# line_sensor_board.net
KiCad netlist of a schematic drawn in EAGLE
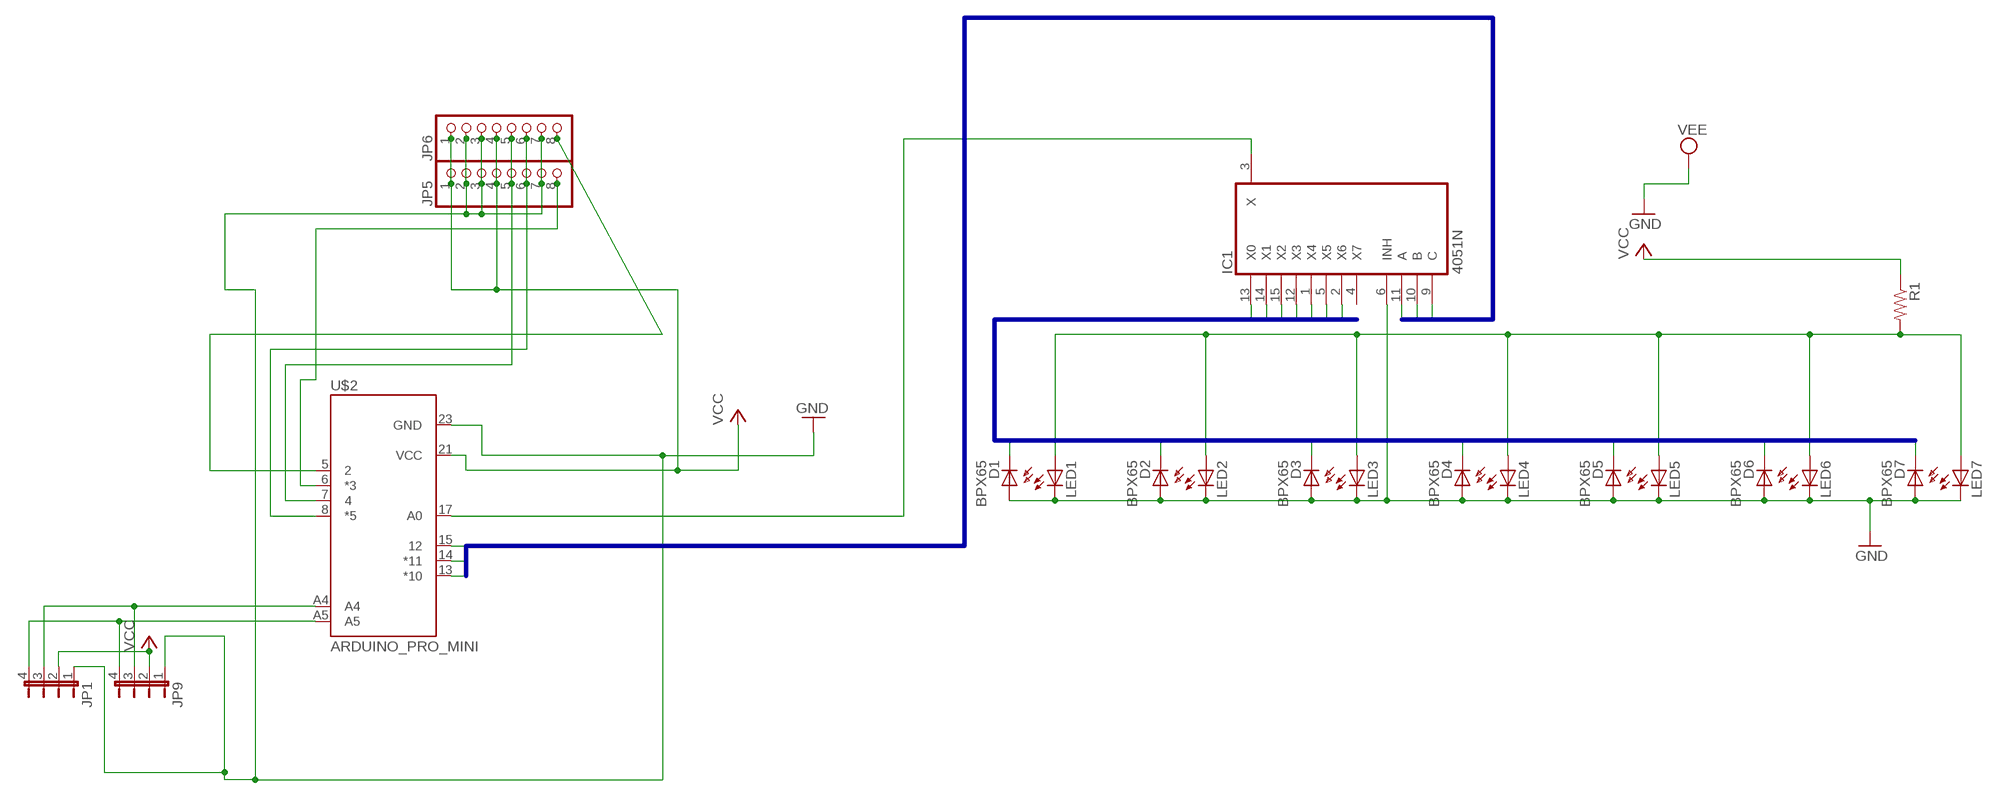
[diagram p0: schematic, sheet 1]

(export (version "E")
  (design (tool "Eeschema 10.0.6"))
  (components
    (comp (ref "D1")
      (value "BPX65")
      (footprint "eagle-import:BPX65")
      (fields (field (name "MPN") "BPX65."))
      (libsource (lib "eagle-import") (part "BPX65"))
    )
    (comp (ref "D2")
      (value "BPX65")
      (footprint "eagle-import:BPX65")
      (fields (field (name "MPN") "BPX65."))
      (libsource (lib "eagle-import") (part "BPX65"))
    )
    (comp (ref "D3")
      (value "BPX65")
      (footprint "eagle-import:BPX65")
      (fields (field (name "MPN") "BPX65."))
      (libsource (lib "eagle-import") (part "BPX65"))
    )
    (comp (ref "D4")
      (value "BPX65")
      (footprint "eagle-import:BPX65")
      (fields (field (name "MPN") "BPX65."))
      (libsource (lib "eagle-import") (part "BPX65"))
    )
    (comp (ref "D5")
      (value "BPX65")
      (footprint "eagle-import:BPX65")
      (fields (field (name "MPN") "BPX65."))
      (libsource (lib "eagle-import") (part "BPX65"))
    )
    (comp (ref "D6")
      (value "BPX65")
      (footprint "eagle-import:BPX65")
      (fields (field (name "MPN") "BPX65."))
      (libsource (lib "eagle-import") (part "BPX65"))
    )
    (comp (ref "D7")
      (value "BPX65")
      (footprint "eagle-import:BPX65")
      (fields (field (name "MPN") "BPX65."))
      (libsource (lib "eagle-import") (part "BPX65"))
    )
    (comp (ref "IC1")
      (value "4051N")
      (footprint "eagle-import:DIL16")
      (libsource (lib "eagle-import") (part "4051N"))
    )
    (comp (ref "JP1")
      (value "JP4E")
      (footprint "eagle-import:JP4")
      (libsource (lib "eagle-import") (part "JP4E"))
    )
    (comp (ref "JP5")
      (value "PINHD-1X8")
      (footprint "eagle-import:1X08")
      (libsource (lib "eagle-import") (part "PINHD-1X8"))
    )
    (comp (ref "JP6")
      (value "PINHD-1X8")
      (footprint "eagle-import:1X08")
      (libsource (lib "eagle-import") (part "PINHD-1X8"))
    )
    (comp (ref "JP9")
      (value "JP4E")
      (footprint "eagle-import:JP4")
      (libsource (lib "eagle-import") (part "JP4E"))
    )
    (comp (ref "LED1")
      (value "LED3MM")
      (footprint "eagle-import:LED3MM")
      (libsource (lib "eagle-import") (part "LED3MM"))
    )
    (comp (ref "LED2")
      (value "LED3MM")
      (footprint "eagle-import:LED3MM")
      (libsource (lib "eagle-import") (part "LED3MM"))
    )
    (comp (ref "LED3")
      (value "LED3MM")
      (footprint "eagle-import:LED3MM")
      (libsource (lib "eagle-import") (part "LED3MM"))
    )
    (comp (ref "LED4")
      (value "LED3MM")
      (footprint "eagle-import:LED3MM")
      (libsource (lib "eagle-import") (part "LED3MM"))
    )
    (comp (ref "LED5")
      (value "LED3MM")
      (footprint "eagle-import:LED3MM")
      (libsource (lib "eagle-import") (part "LED3MM"))
    )
    (comp (ref "LED6")
      (value "LED3MM")
      (footprint "eagle-import:LED3MM")
      (libsource (lib "eagle-import") (part "LED3MM"))
    )
    (comp (ref "LED7")
      (value "LED3MM")
      (footprint "eagle-import:LED3MM")
      (libsource (lib "eagle-import") (part "LED3MM"))
    )
    (comp (ref "R1")
      (value "R-US_0204/5")
      (footprint "eagle-import:0204_5")
      (libsource (lib "eagle-import") (part "R-US_0204/5"))
    )
    (comp (ref "U$2")
      (value "ARDUINO_PRO_MINI")
      (footprint "eagle-import:ARDUINO_PRO_MINI")
      (libsource (lib "eagle-import") (part "ARDUINO_PRO_MINI"))
    )
  )
  (nets
    (net (code "1") (name "/A1") (class "Default")
      (node (ref "IC1") (pin "11") (pinfunction "A_11") (pintype "input"))
      (node (ref "U$2") (pin "15") (pinfunction "12_15") (pintype "bidirectional"))
    )
    (net (code "2") (name "/A2") (class "Default")
      (node (ref "IC1") (pin "10") (pinfunction "B_10") (pintype "input"))
      (node (ref "U$2") (pin "14") (pinfunction "*11_14") (pintype "bidirectional"))
    )
    (net (code "3") (name "/A3") (class "Default")
      (node (ref "IC1") (pin "9") (pinfunction "C_9") (pintype "input"))
      (node (ref "U$2") (pin "13") (pinfunction "*10_13") (pintype "bidirectional"))
    )
    (net (code "4") (name "/B1") (class "Default")
      (node (ref "D7") (pin "K") (pinfunction "C_K") (pintype "passive"))
      (node (ref "IC1") (pin "13") (pinfunction "X0_13") (pintype "bidirectional"))
    )
    (net (code "5") (name "/B2") (class "Default")
      (node (ref "D6") (pin "K") (pinfunction "C_K") (pintype "passive"))
      (node (ref "IC1") (pin "14") (pinfunction "X1_14") (pintype "bidirectional"))
    )
    (net (code "6") (name "/B3") (class "Default")
      (node (ref "D5") (pin "K") (pinfunction "C_K") (pintype "passive"))
      (node (ref "IC1") (pin "15") (pinfunction "X2_15") (pintype "bidirectional"))
    )
    (net (code "7") (name "/B4") (class "Default")
      (node (ref "D4") (pin "K") (pinfunction "C_K") (pintype "passive"))
      (node (ref "IC1") (pin "12") (pinfunction "X3_12") (pintype "bidirectional"))
    )
    (net (code "8") (name "/B5") (class "Default")
      (node (ref "D3") (pin "K") (pinfunction "C_K") (pintype "passive"))
      (node (ref "IC1") (pin "1") (pinfunction "X4_1") (pintype "bidirectional"))
    )
    (net (code "9") (name "/B6") (class "Default")
      (node (ref "D2") (pin "K") (pinfunction "C_K") (pintype "passive"))
      (node (ref "IC1") (pin "5") (pinfunction "X5_5") (pintype "bidirectional"))
    )
    (net (code "10") (name "/B7") (class "Default")
      (node (ref "D1") (pin "K") (pinfunction "C_K") (pintype "passive"))
      (node (ref "IC1") (pin "2") (pinfunction "X6_2") (pintype "bidirectional"))
    )
    (net (code "11") (name "GND") (class "Default")
      (node (ref "D1") (pin "A") (pinfunction "A_A") (pintype "passive"))
      (node (ref "D2") (pin "A") (pinfunction "A_A") (pintype "passive"))
      (node (ref "D3") (pin "A") (pinfunction "A_A") (pintype "passive"))
      (node (ref "D4") (pin "A") (pinfunction "A_A") (pintype "passive"))
      (node (ref "D5") (pin "A") (pinfunction "A_A") (pintype "passive"))
      (node (ref "D6") (pin "A") (pinfunction "A_A") (pintype "passive"))
      (node (ref "D7") (pin "A") (pinfunction "A_A") (pintype "passive"))
      (node (ref "IC1") (pin "6") (pinfunction "INH_6") (pintype "input"))
      (node (ref "JP1") (pin "1") (pinfunction "1_1") (pintype "passive"))
      (node (ref "JP5") (pin "2") (pinfunction "2_2") (pintype "passive"))
      (node (ref "JP5") (pin "3") (pinfunction "3_3") (pintype "passive"))
      (node (ref "JP5") (pin "7") (pinfunction "7_7") (pintype "passive"))
      (node (ref "JP6") (pin "2") (pinfunction "2_2") (pintype "passive"))
      (node (ref "JP6") (pin "3") (pinfunction "3_3") (pintype "passive"))
      (node (ref "JP6") (pin "7") (pinfunction "7_7") (pintype "passive"))
      (node (ref "JP9") (pin "1") (pinfunction "1_1") (pintype "passive"))
      (node (ref "LED1") (pin "K") (pinfunction "C_K") (pintype "passive"))
      (node (ref "LED2") (pin "K") (pinfunction "C_K") (pintype "passive"))
      (node (ref "LED3") (pin "K") (pinfunction "C_K") (pintype "passive"))
      (node (ref "LED4") (pin "K") (pinfunction "C_K") (pintype "passive"))
      (node (ref "LED5") (pin "K") (pinfunction "C_K") (pintype "passive"))
      (node (ref "LED6") (pin "K") (pinfunction "C_K") (pintype "passive"))
      (node (ref "LED7") (pin "K") (pinfunction "C_K") (pintype "passive"))
      (node (ref "U$2") (pin "23") (pinfunction "GND_23") (pintype "bidirectional"))
    )
    (net (code "12") (name "Net-(IC1A-X)") (class "Default")
      (node (ref "IC1") (pin "3") (pinfunction "X_3") (pintype "bidirectional"))
      (node (ref "U$2") (pin "17") (pinfunction "A0_17") (pintype "bidirectional"))
    )
    (net (code "13") (name "Net-(JP1-Pad3)") (class "Default")
      (node (ref "JP1") (pin "3") (pinfunction "3_3") (pintype "passive"))
      (node (ref "JP9") (pin "3") (pinfunction "3_3") (pintype "passive"))
      (node (ref "U$2") (pin "A4") (pinfunction "A4_A4") (pintype "bidirectional"))
    )
    (net (code "14") (name "Net-(JP1-Pad4)") (class "Default")
      (node (ref "JP1") (pin "4") (pinfunction "4_4") (pintype "passive"))
      (node (ref "JP9") (pin "4") (pinfunction "4_4") (pintype "passive"))
      (node (ref "U$2") (pin "A5") (pinfunction "A5_A5") (pintype "bidirectional"))
    )
    (net (code "15") (name "Net-(LED1-PadA)") (class "Default")
      (node (ref "LED1") (pin "A") (pinfunction "A_A") (pintype "passive"))
      (node (ref "LED2") (pin "A") (pinfunction "A_A") (pintype "passive"))
      (node (ref "LED3") (pin "A") (pinfunction "A_A") (pintype "passive"))
      (node (ref "LED4") (pin "A") (pinfunction "A_A") (pintype "passive"))
      (node (ref "LED5") (pin "A") (pinfunction "A_A") (pintype "passive"))
      (node (ref "LED6") (pin "A") (pinfunction "A_A") (pintype "passive"))
      (node (ref "LED7") (pin "A") (pinfunction "A_A") (pintype "passive"))
      (node (ref "R1") (pin "2") (pinfunction "2_2") (pintype "passive"))
    )
    (net (code "16") (name "Net-(U$2-*3)") (class "Default")
      (node (ref "JP5") (pin "8") (pinfunction "8_8") (pintype "passive"))
      (node (ref "U$2") (pin "6") (pinfunction "*3_6") (pintype "bidirectional"))
    )
    (net (code "17") (name "Net-(U$2-*5)") (class "Default")
      (node (ref "JP5") (pin "6") (pinfunction "6_6") (pintype "passive"))
      (node (ref "JP6") (pin "6") (pinfunction "6_6") (pintype "passive"))
      (node (ref "U$2") (pin "8") (pinfunction "*5_8") (pintype "bidirectional"))
    )
    (net (code "18") (name "Net-(U$2-2)") (class "Default")
      (node (ref "JP6") (pin "8") (pinfunction "8_8") (pintype "passive"))
      (node (ref "U$2") (pin "5") (pinfunction "2_5") (pintype "bidirectional"))
    )
    (net (code "19") (name "Net-(U$2-4)") (class "Default")
      (node (ref "JP5") (pin "5") (pinfunction "5_5") (pintype "passive"))
      (node (ref "JP6") (pin "5") (pinfunction "5_5") (pintype "passive"))
      (node (ref "U$2") (pin "7") (pinfunction "4_7") (pintype "bidirectional"))
    )
    (net (code "20") (name "VCC") (class "Default")
      (node (ref "JP1") (pin "2") (pinfunction "2_2") (pintype "passive"))
      (node (ref "JP5") (pin "1") (pinfunction "1_1") (pintype "passive"))
      (node (ref "JP5") (pin "4") (pinfunction "4_4") (pintype "passive"))
      (node (ref "JP6") (pin "1") (pinfunction "1_1") (pintype "passive"))
      (node (ref "JP6") (pin "4") (pinfunction "4_4") (pintype "passive"))
      (node (ref "JP9") (pin "2") (pinfunction "2_2") (pintype "passive"))
      (node (ref "R1") (pin "1") (pinfunction "1_1") (pintype "passive"))
      (node (ref "U$2") (pin "21") (pinfunction "VCC_21") (pintype "bidirectional"))
    )
    (net (code "21") (name "unconnected-(IC1A-X7-Pad4)") (class "Default")
      (node (ref "IC1") (pin "4") (pinfunction "X7_4") (pintype "bidirectional"))
    )
  )
)
